# Raspi_Feather.net
KiCad netlist of a schematic drawn in EAGLE
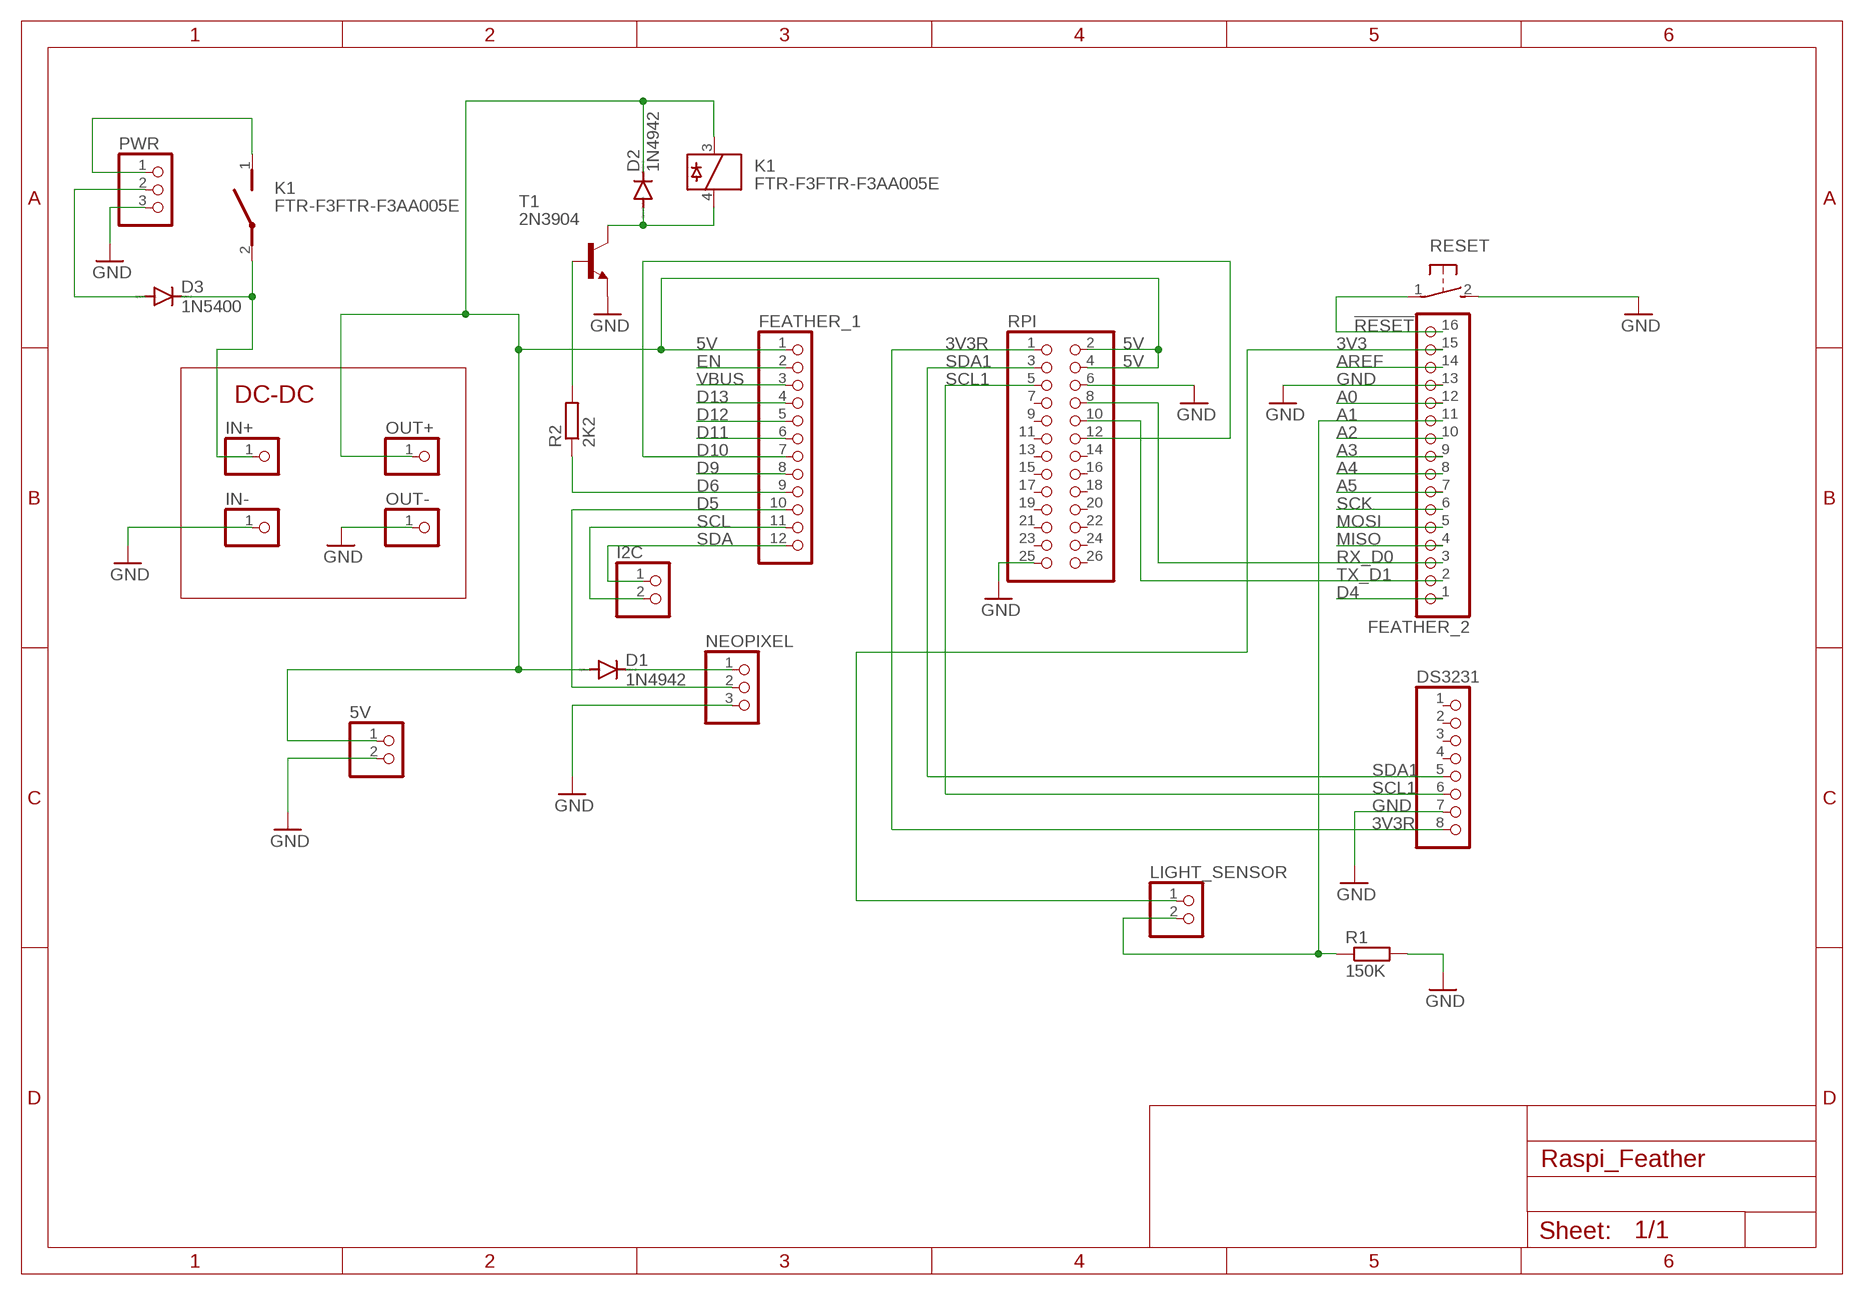
[diagram p0: schematic, sheet 1]

(export (version "E")
  (design (tool "Eeschema 10.0.6"))
  (components
    (comp (ref "5V")
      (value "PINHD-1X2")
      (footprint "eagle-import:1X02")
      (libsource (lib "eagle-import") (part "PINHD-1X2"))
    )
    (comp (ref "D1")
      (value "1N4942")
      (footprint "eagle-import:DO41-10")
      (libsource (lib "eagle-import") (part "1N4942"))
    )
    (comp (ref "D2")
      (value "1N4942")
      (footprint "eagle-import:DO41-10")
      (libsource (lib "eagle-import") (part "1N4942"))
    )
    (comp (ref "D3")
      (value "1N5400")
      (footprint "eagle-import:DO201-15")
      (libsource (lib "eagle-import") (part "1N5400"))
    )
    (comp (ref "DS3231")
      (value "PINHD-1X8")
      (footprint "eagle-import:1X08")
      (libsource (lib "eagle-import") (part "PINHD-1X8"))
    )
    (comp (ref "FEATHER_1")
      (value "HEADER-1X12")
      (footprint "eagle-import:1X12_ROUND")
      (libsource (lib "eagle-import") (part "HEADER-1X12"))
    )
    (comp (ref "FEATHER_2")
      (value "HEADER-1X16ROUND")
      (footprint "eagle-import:1X16_ROUND")
      (libsource (lib "eagle-import") (part "HEADER-1X16ROUND"))
    )
    (comp (ref "I2C")
      (value "PINHD-1X2")
      (footprint "eagle-import:1X02")
      (libsource (lib "eagle-import") (part "PINHD-1X2"))
    )
    (comp (ref "IN+")
      (value "PINHD-1X1")
      (footprint "eagle-import:1X01")
      (libsource (lib "eagle-import") (part "PINHD-1X1"))
    )
    (comp (ref "IN-")
      (value "PINHD-1X1")
      (footprint "eagle-import:1X01")
      (libsource (lib "eagle-import") (part "PINHD-1X1"))
    )
    (comp (ref "K1")
      (value "FTR-F3FTR-F3AA005E")
      (footprint "eagle-import:REED")
      (libsource (lib "eagle-import") (part "FTR-F3FTR-F3AA005E"))
    )
    (comp (ref "LIGHT_SENSOR")
      (value "PINHD-1X2")
      (footprint "eagle-import:1X02")
      (libsource (lib "eagle-import") (part "PINHD-1X2"))
    )
    (comp (ref "NEOPIXEL")
      (value "PINHD-1X3")
      (footprint "eagle-import:1X03")
      (libsource (lib "eagle-import") (part "PINHD-1X3"))
    )
    (comp (ref "OUT+")
      (value "PINHD-1X1")
      (footprint "eagle-import:1X01")
      (libsource (lib "eagle-import") (part "PINHD-1X1"))
    )
    (comp (ref "OUT-")
      (value "PINHD-1X1")
      (footprint "eagle-import:1X01")
      (libsource (lib "eagle-import") (part "PINHD-1X1"))
    )
    (comp (ref "PWR")
      (value "PINHD-1X3")
      (footprint "eagle-import:1X03")
      (libsource (lib "eagle-import") (part "PINHD-1X3"))
    )
    (comp (ref "R1")
      (value "150K")
      (footprint "eagle-import:0207_7")
      (libsource (lib "eagle-import") (part "R-EU_0207/7"))
    )
    (comp (ref "R2")
      (value "2K2")
      (footprint "eagle-import:0207_10")
      (libsource (lib "eagle-import") (part "R-EU_0207/10"))
    )
    (comp (ref "RESET")
      (value "31-XX")
      (footprint "eagle-import:B3F-31XX")
      (fields (field (name "MPN") "B3F-3100"))
      (libsource (lib "eagle-import") (part "31-XX"))
    )
    (comp (ref "RPI")
      (value "PINHD-2X13")
      (footprint "eagle-import:2X13")
      (libsource (lib "eagle-import") (part "PINHD-2X13"))
    )
    (comp (ref "T1")
      (value "2N3904")
      (footprint "eagle-import:TO92")
      (libsource (lib "eagle-import") (part "2N3904"))
    )
  )
  (nets
    (net (code "1") (name "/3V3") (class "Default")
      (node (ref "FEATHER_2") (pin "15") (pinfunction "15_15") (pintype "passive"))
      (node (ref "LIGHT_SENSOR") (pin "1") (pinfunction "1_1") (pintype "passive"))
    )
    (net (code "2") (name "/3V3R") (class "Default")
      (node (ref "DS3231") (pin "8") (pinfunction "8_8") (pintype "passive"))
      (node (ref "RPI") (pin "1") (pinfunction "1_1") (pintype "passive"))
    )
    (net (code "3") (name "/5V") (class "Default")
      (node (ref "5V") (pin "1") (pinfunction "1_1") (pintype "passive"))
      (node (ref "D1") (pin "A") (pinfunction "A_A") (pintype "passive"))
      (node (ref "D2") (pin "C") (pinfunction "C_C") (pintype "passive"))
      (node (ref "FEATHER_1") (pin "1") (pinfunction "1_1") (pintype "passive"))
      (node (ref "K1") (pin "3") (pinfunction "3_3") (pintype "passive"))
      (node (ref "OUT+") (pin "1") (pinfunction "1_1") (pintype "passive"))
      (node (ref "RPI") (pin "2") (pinfunction "2_2") (pintype "passive"))
      (node (ref "RPI") (pin "4") (pinfunction "4_4") (pintype "passive"))
    )
    (net (code "4") (name "/A0") (class "Default")
      (node (ref "FEATHER_2") (pin "12") (pinfunction "12_12") (pintype "passive"))
    )
    (net (code "5") (name "/A1") (class "Default")
      (node (ref "FEATHER_2") (pin "11") (pinfunction "11_11") (pintype "passive"))
      (node (ref "LIGHT_SENSOR") (pin "2") (pinfunction "2_2") (pintype "passive"))
      (node (ref "R1") (pin "1") (pinfunction "1_1") (pintype "passive"))
    )
    (net (code "6") (name "/A2") (class "Default")
      (node (ref "FEATHER_2") (pin "10") (pinfunction "10_10") (pintype "passive"))
    )
    (net (code "7") (name "/A3") (class "Default")
      (node (ref "FEATHER_2") (pin "9") (pinfunction "9_9") (pintype "passive"))
    )
    (net (code "8") (name "/A4") (class "Default")
      (node (ref "FEATHER_2") (pin "8") (pinfunction "8_8") (pintype "passive"))
    )
    (net (code "9") (name "/A5") (class "Default")
      (node (ref "FEATHER_2") (pin "7") (pinfunction "7_7") (pintype "passive"))
    )
    (net (code "10") (name "/AREF") (class "Default")
      (node (ref "FEATHER_2") (pin "14") (pinfunction "14_14") (pintype "passive"))
    )
    (net (code "11") (name "/D4") (class "Default")
      (node (ref "FEATHER_2") (pin "1") (pinfunction "1_1") (pintype "passive"))
    )
    (net (code "12") (name "/D5") (class "Default")
      (node (ref "FEATHER_1") (pin "10") (pinfunction "10_10") (pintype "passive"))
      (node (ref "NEOPIXEL") (pin "2") (pinfunction "2_2") (pintype "passive"))
    )
    (net (code "13") (name "/D6") (class "Default")
      (node (ref "FEATHER_1") (pin "9") (pinfunction "9_9") (pintype "passive"))
      (node (ref "R2") (pin "1") (pinfunction "1_1") (pintype "passive"))
    )
    (net (code "14") (name "/D9") (class "Default")
      (node (ref "FEATHER_1") (pin "8") (pinfunction "8_8") (pintype "passive"))
    )
    (net (code "15") (name "/D10") (class "Default")
      (node (ref "FEATHER_1") (pin "7") (pinfunction "7_7") (pintype "passive"))
      (node (ref "RPI") (pin "12") (pinfunction "12_12") (pintype "passive"))
    )
    (net (code "16") (name "/D11") (class "Default")
      (node (ref "FEATHER_1") (pin "6") (pinfunction "6_6") (pintype "passive"))
    )
    (net (code "17") (name "/D12") (class "Default")
      (node (ref "FEATHER_1") (pin "5") (pinfunction "5_5") (pintype "passive"))
    )
    (net (code "18") (name "/D13") (class "Default")
      (node (ref "FEATHER_1") (pin "4") (pinfunction "4_4") (pintype "passive"))
    )
    (net (code "19") (name "/EN") (class "Default")
      (node (ref "FEATHER_1") (pin "2") (pinfunction "2_2") (pintype "passive"))
    )
    (net (code "20") (name "/MISO") (class "Default")
      (node (ref "FEATHER_2") (pin "4") (pinfunction "4_4") (pintype "passive"))
    )
    (net (code "21") (name "/MOSI") (class "Default")
      (node (ref "FEATHER_2") (pin "5") (pinfunction "5_5") (pintype "passive"))
    )
    (net (code "22") (name "/RX_D0") (class "Default")
      (node (ref "FEATHER_2") (pin "3") (pinfunction "3_3") (pintype "passive"))
      (node (ref "RPI") (pin "8") (pinfunction "8_8") (pintype "passive"))
    )
    (net (code "23") (name "/SCK") (class "Default")
      (node (ref "FEATHER_2") (pin "6") (pinfunction "6_6") (pintype "passive"))
    )
    (net (code "24") (name "/SCL") (class "Default")
      (node (ref "FEATHER_1") (pin "11") (pinfunction "11_11") (pintype "passive"))
      (node (ref "I2C") (pin "2") (pinfunction "2_2") (pintype "passive"))
    )
    (net (code "25") (name "/SCL1") (class "Default")
      (node (ref "DS3231") (pin "6") (pinfunction "6_6") (pintype "passive"))
      (node (ref "RPI") (pin "5") (pinfunction "5_5") (pintype "passive"))
    )
    (net (code "26") (name "/SDA") (class "Default")
      (node (ref "FEATHER_1") (pin "12") (pinfunction "12_12") (pintype "passive"))
      (node (ref "I2C") (pin "1") (pinfunction "1_1") (pintype "passive"))
    )
    (net (code "27") (name "/SDA1") (class "Default")
      (node (ref "DS3231") (pin "5") (pinfunction "5_5") (pintype "passive"))
      (node (ref "RPI") (pin "3") (pinfunction "3_3") (pintype "passive"))
    )
    (net (code "28") (name "/TX_D1") (class "Default")
      (node (ref "FEATHER_2") (pin "2") (pinfunction "2_2") (pintype "passive"))
      (node (ref "RPI") (pin "10") (pinfunction "10_10") (pintype "passive"))
    )
    (net (code "29") (name "/VBUS") (class "Default")
      (node (ref "FEATHER_1") (pin "3") (pinfunction "3_3") (pintype "passive"))
    )
    (net (code "30") (name "/~{RESET}") (class "Default")
      (node (ref "FEATHER_2") (pin "16") (pinfunction "16_16") (pintype "passive"))
      (node (ref "RESET") (pin "1") (pinfunction "P_1") (pintype "passive"))
    )
    (net (code "31") (name "GND") (class "Default")
      (node (ref "5V") (pin "2") (pinfunction "2_2") (pintype "passive"))
      (node (ref "DS3231") (pin "7") (pinfunction "7_7") (pintype "passive"))
      (node (ref "FEATHER_2") (pin "13") (pinfunction "13_13") (pintype "passive"))
      (node (ref "IN-") (pin "1") (pinfunction "1_1") (pintype "passive"))
      (node (ref "NEOPIXEL") (pin "3") (pinfunction "3_3") (pintype "passive"))
      (node (ref "OUT-") (pin "1") (pinfunction "1_1") (pintype "passive"))
      (node (ref "PWR") (pin "3") (pinfunction "3_3") (pintype "passive"))
      (node (ref "R1") (pin "2") (pinfunction "2_2") (pintype "passive"))
      (node (ref "RESET") (pin "2") (pinfunction "S_2") (pintype "passive"))
      (node (ref "RPI") (pin "25") (pinfunction "25_25") (pintype "passive"))
      (node (ref "RPI") (pin "6") (pinfunction "6_6") (pintype "passive"))
      (node (ref "T1") (pin "3") (pinfunction "E_3") (pintype "passive"))
    )
    (net (code "32") (name "Net-(D1-PadC)") (class "Default")
      (node (ref "D1") (pin "C") (pinfunction "C_C") (pintype "passive"))
      (node (ref "NEOPIXEL") (pin "1") (pinfunction "1_1") (pintype "passive"))
    )
    (net (code "33") (name "Net-(D3-PadA)") (class "Default")
      (node (ref "D3") (pin "A") (pinfunction "A_A") (pintype "passive"))
      (node (ref "PWR") (pin "2") (pinfunction "2_2") (pintype "passive"))
    )
    (net (code "34") (name "Net-(D3-PadC)") (class "Default")
      (node (ref "D3") (pin "C") (pinfunction "C_C") (pintype "passive"))
      (node (ref "IN+") (pin "1") (pinfunction "1_1") (pintype "passive"))
      (node (ref "K1") (pin "2") (pinfunction "2_2") (pintype "passive"))
    )
    (net (code "35") (name "Net-(K1-Pad1)") (class "Default")
      (node (ref "K1") (pin "1") (pinfunction "1_1") (pintype "passive"))
      (node (ref "PWR") (pin "1") (pinfunction "1_1") (pintype "passive"))
    )
    (net (code "36") (name "Net-(T1-B)") (class "Default")
      (node (ref "R2") (pin "2") (pinfunction "2_2") (pintype "passive"))
      (node (ref "T1") (pin "2") (pinfunction "B_2") (pintype "passive"))
    )
    (net (code "37") (name "Net-(T1-C)") (class "Default")
      (node (ref "D2") (pin "A") (pinfunction "A_A") (pintype "passive"))
      (node (ref "K1") (pin "4") (pinfunction "4_4") (pintype "passive"))
      (node (ref "T1") (pin "1") (pinfunction "C_1") (pintype "passive"))
    )
    (net (code "38") (name "unconnected-(DS3231-Pad1)") (class "Default")
      (node (ref "DS3231") (pin "1") (pinfunction "1_1") (pintype "passive"))
    )
    (net (code "39") (name "unconnected-(DS3231-Pad2)") (class "Default")
      (node (ref "DS3231") (pin "2") (pinfunction "2_2") (pintype "passive"))
    )
    (net (code "40") (name "unconnected-(DS3231-Pad3)") (class "Default")
      (node (ref "DS3231") (pin "3") (pinfunction "3_3") (pintype "passive"))
    )
    (net (code "41") (name "unconnected-(DS3231-Pad4)") (class "Default")
      (node (ref "DS3231") (pin "4") (pinfunction "4_4") (pintype "passive"))
    )
    (net (code "42") (name "unconnected-(RPI-Pad7)") (class "Default")
      (node (ref "RPI") (pin "7") (pinfunction "7_7") (pintype "passive"))
    )
    (net (code "43") (name "unconnected-(RPI-Pad9)") (class "Default")
      (node (ref "RPI") (pin "9") (pinfunction "9_9") (pintype "passive"))
    )
    (net (code "44") (name "unconnected-(RPI-Pad11)") (class "Default")
      (node (ref "RPI") (pin "11") (pinfunction "11_11") (pintype "passive"))
    )
    (net (code "45") (name "unconnected-(RPI-Pad13)") (class "Default")
      (node (ref "RPI") (pin "13") (pinfunction "13_13") (pintype "passive"))
    )
    (net (code "46") (name "unconnected-(RPI-Pad14)") (class "Default")
      (node (ref "RPI") (pin "14") (pinfunction "14_14") (pintype "passive"))
    )
    (net (code "47") (name "unconnected-(RPI-Pad15)") (class "Default")
      (node (ref "RPI") (pin "15") (pinfunction "15_15") (pintype "passive"))
    )
    (net (code "48") (name "unconnected-(RPI-Pad16)") (class "Default")
      (node (ref "RPI") (pin "16") (pinfunction "16_16") (pintype "passive"))
    )
    (net (code "49") (name "unconnected-(RPI-Pad17)") (class "Default")
      (node (ref "RPI") (pin "17") (pinfunction "17_17") (pintype "passive"))
    )
    (net (code "50") (name "unconnected-(RPI-Pad18)") (class "Default")
      (node (ref "RPI") (pin "18") (pinfunction "18_18") (pintype "passive"))
    )
    (net (code "51") (name "unconnected-(RPI-Pad19)") (class "Default")
      (node (ref "RPI") (pin "19") (pinfunction "19_19") (pintype "passive"))
    )
    (net (code "52") (name "unconnected-(RPI-Pad20)") (class "Default")
      (node (ref "RPI") (pin "20") (pinfunction "20_20") (pintype "passive"))
    )
    (net (code "53") (name "unconnected-(RPI-Pad21)") (class "Default")
      (node (ref "RPI") (pin "21") (pinfunction "21_21") (pintype "passive"))
    )
    (net (code "54") (name "unconnected-(RPI-Pad22)") (class "Default")
      (node (ref "RPI") (pin "22") (pinfunction "22_22") (pintype "passive"))
    )
    (net (code "55") (name "unconnected-(RPI-Pad23)") (class "Default")
      (node (ref "RPI") (pin "23") (pinfunction "23_23") (pintype "passive"))
    )
    (net (code "56") (name "unconnected-(RPI-Pad24)") (class "Default")
      (node (ref "RPI") (pin "24") (pinfunction "24_24") (pintype "passive"))
    )
    (net (code "57") (name "unconnected-(RPI-Pad26)") (class "Default")
      (node (ref "RPI") (pin "26") (pinfunction "26_26") (pintype "passive"))
    )
  )
)
